# USBWandler.net
KiCad netlist of a schematic drawn in Altium Designer
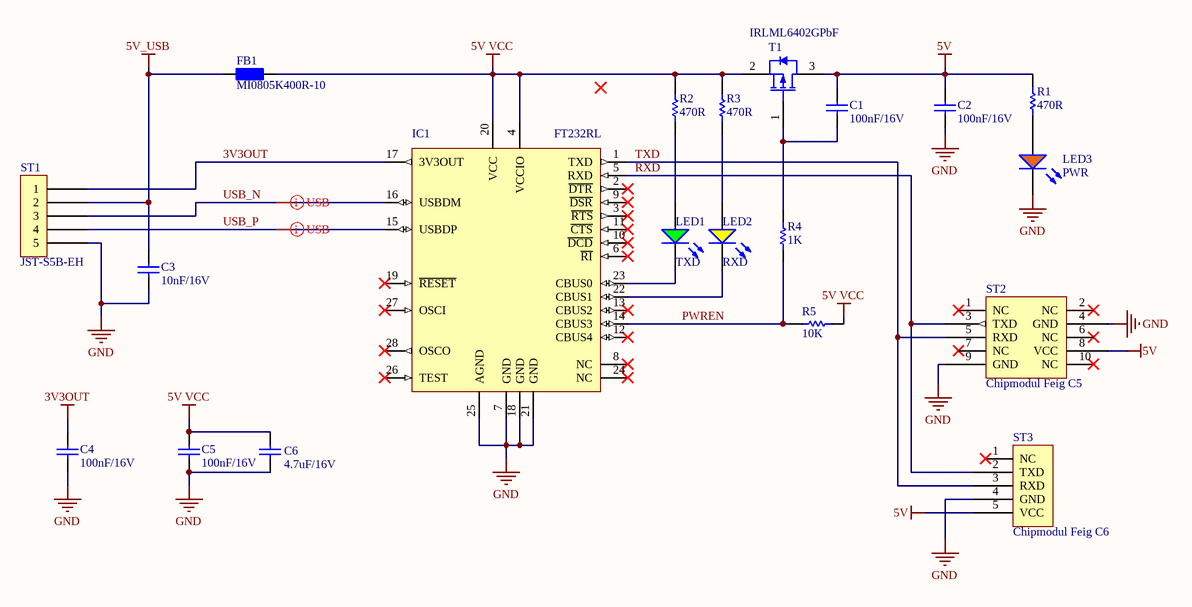
[diagram p0: USBWandler.SchDoc]

(export (version "E")
  (design (tool "Eeschema 10.0.6"))
  (components
    (comp (ref "C1")
      (value "100nF/16V")
      (footprint "CAPC0805(2012)145_M")
      (description "CAP 100nF 16V ±10% 0805 (2012 Metric) Thickness 1.45mm SMD")
      (fields (field (name "TOLERANCE") "Â±10%"))
      (libsource (lib "Altium Content Vault") (part "CMP-1036-04401-1"))
    )
    (comp (ref "C2")
      (value "100nF/16V")
      (footprint "CAPC0805(2012)145_M")
      (description "CAP 100nF 16V ±10% 0805 (2012 Metric) Thickness 1.45mm SMD")
      (fields (field (name "TOLERANCE") "Â±10%"))
      (libsource (lib "Altium Content Vault") (part "CMP-1036-04401-1"))
    )
    (comp (ref "C3")
      (value "10nF/16V")
      (footprint "CAPC0805(2012)145_L")
      (description "CAP 10nF 16V ±1% 0805 (2012 Metric) Thickness 1.45mm SMD")
      (fields (field (name "TOLERANCE") "Â±1%"))
      (libsource (lib "Altium Content Vault") (part "CMP-1036-03813-1"))
    )
    (comp (ref "C4")
      (value "100nF/16V")
      (footprint "CAPC0805(2012)145_M")
      (description "CAP 100nF 16V ±10% 0805 (2012 Metric) Thickness 1.45mm SMD")
      (fields (field (name "TOLERANCE") "Â±10%"))
      (libsource (lib "Altium Content Vault") (part "CMP-1036-04401-1"))
    )
    (comp (ref "C5")
      (value "100nF/16V")
      (footprint "CAPC0805(2012)145_M")
      (description "CAP 100nF 16V ±10% 0805 (2012 Metric) Thickness 1.45mm SMD")
      (fields (field (name "TOLERANCE") "Â±10%"))
      (libsource (lib "Altium Content Vault") (part "CMP-1036-04401-1"))
    )
    (comp (ref "C6")
      (value "4.7uF/16V")
      (footprint "CAPC1206(3216)190_L")
      (description "CAP 4.7uF 16V ±20% 1206 (3216 Metric) Thickness 1.9mm SMD")
      (fields (field (name "TOLERANCE") "Â±20%"))
      (libsource (lib "Altium Content Vault") (part "CMP-1037-04912-1"))
    )
    (comp (ref "FB1")
      (value "MI0805K400R-10")
      (footprint "L0805 (2012)")
      (description "Ferrite Chip Beads MI0805K400R-10, 0805, 40 ohm, 1,5A")
      (libsource (lib "FroH1") (part "Ferrit Bead MI0805K400R-10"))
    )
    (comp (ref "IC1")
      (value "FT232RL")
      (footprint "SSOP-28_M")
      (description "USB UART Asynchronous Serial Data Transfer Chip, 28-pin SSOP, Tape and Reel")
      (fields (field (name "PARTNUMBER") "FT232RL-Reel") (field (name "MANUFACTURER") "FTDI"))
      (libsource (lib "Altium Content Vault") (part "CMP-0078-00029-3"))
    )
    (comp (ref "LED1")
      (value "TXD")
      (footprint "LTST-C170GKT_V")
      (description "LED GREEN CLEAR 0805 SMD")
      (fields (field (name "PARTNUMBER") "LTST-C170GKT"))
      (libsource (lib "Altium Content Vault") (part "CMP-1674-00002-2"))
    )
    (comp (ref "LED2")
      (value "RXD")
      (footprint "LTST-C170YKT_V")
      (description "LED YELLOW CLEAR 0805 SMD")
      (fields (field (name "MANUFACTURER") "Lite-On") (field (name "PARTNUMBER") "LTST-C170YKT"))
      (libsource (lib "Altium Content Vault") (part "CMP-1674-00003-3"))
    )
    (comp (ref "LED3")
      (value "PWR")
      (footprint "LTST-C171AKT_V")
      (description "LED AMBER CLR THIN 0805 SMD")
      (fields (field (name "PARTNUMBER") "LTST-C171AKT") (field (name "MANUFACTURER") "Lite-On"))
      (libsource (lib "Altium Content Vault") (part "CMP-1674-00004-3"))
    )
    (comp (ref "R1")
      (value "470R")
      (footprint "RESC0805(2012)_N")
      (description "470R 0.125W 1% 0805 (2012 Metric)  SMD")
      (fields (field (name "POWER") "0.125 W") (field (name "TOLERANCE") "1 %"))
      (libsource (lib "Altium Content Vault") (part "CMP-1013-00473-1"))
    )
    (comp (ref "R2")
      (value "470R")
      (footprint "RESC0805(2012)_N")
      (description "470R 0.125W 1% 0805 (2012 Metric)  SMD")
      (fields (field (name "POWER") "0.125 W") (field (name "TOLERANCE") "1 %"))
      (libsource (lib "Altium Content Vault") (part "CMP-1013-00473-1"))
    )
    (comp (ref "R3")
      (value "470R")
      (footprint "RESC0805(2012)_N")
      (description "470R 0.125W 1% 0805 (2012 Metric)  SMD")
      (fields (field (name "POWER") "0.125 W") (field (name "TOLERANCE") "1 %"))
      (libsource (lib "Altium Content Vault") (part "CMP-1013-00473-1"))
    )
    (comp (ref "R4")
      (value "1K")
      (footprint "RESC0805(2012)_M")
      (description "1K 0.125W 1% 0805 (2012 Metric)  SMD")
      (fields (field (name "TOLERANCE") "1 %") (field (name "POWER") "0.125 W"))
      (libsource (lib "Altium Content Vault") (part "CMP-1013-00510-1"))
    )
    (comp (ref "R5")
      (value "10K")
      (footprint "RESC0805(2012)_M")
      (description "10K 0.125W 1% 0805 (2012 Metric)  SMD")
      (fields (field (name "TOLERANCE") "1 %") (field (name "POWER") "0.125 W"))
      (libsource (lib "Altium Content Vault") (part "CMP-1013-00623-1"))
    )
    (comp (ref "ST1")
      (value "JST-S5B-EH")
      (footprint "JST-S5B-EH")
      (description "JST EH Connector RM=2,5mm, Side Entry Type")
      (libsource (lib "FroH1") (part "JST-S5B-EH"))
    )
    (comp (ref "ST2")
      (value "Chipmodul Feig C5")
      (footprint "FroH1:ChipModul Feig C5")
      (description "Feig Chipmodul CPR.02")
      (libsource (lib "FroH1") (part "Chipmodul Feig C5"))
    )
    (comp (ref "ST3")
      (value "Chipmodul Feig C6")
      (footprint "ChipModul Feig C6")
      (libsource (lib "FroH1") (part "Chipmodul Feig C6"))
    )
    (comp (ref "T1")
      (value "IRLML6402GPbF")
      (footprint "INTR-SOT-23-3_V")
      (description "HEXFET Power MOSFET, P-Channel, -20 V VDSS, 0.065 Ohm RDS, 3-Pin SOT23, RoHS, Tape and Reel")
      (fields (field (name "MANUFACTURER") "International Rectifier"))
      (libsource (lib "Altium Content Vault") (part "CMP-0676-00001-1"))
    )
  )
  (nets
    (net (code "1") (name "/PWREN") (class "Default")
      (node (ref "IC1") (pin "14") (pinfunction "CBUS3_14") (pintype "bidirectional"))
      (node (ref "R4") (pin "1") (pinfunction "1_1") (pintype "passive"))
      (node (ref "R5") (pin "2") (pinfunction "2_2") (pintype "passive"))
    )
    (net (code "2") (name "/RXD") (class "Default")
      (node (ref "IC1") (pin "5") (pinfunction "RXD_5") (pintype "input"))
      (node (ref "ST2") (pin "3") (pinfunction "TXD_3") (pintype "output"))
      (node (ref "ST3") (pin "2") (pinfunction "TXD_2") (pintype "passive"))
    )
    (net (code "3") (name "/TXD") (class "Default")
      (node (ref "IC1") (pin "1") (pinfunction "TXD_1") (pintype "output"))
      (node (ref "ST2") (pin "5") (pinfunction "RXD_5") (pintype "passive"))
      (node (ref "ST3") (pin "3") (pinfunction "RXD_3") (pintype "passive"))
    )
    (net (code "4") (name "/USB_N") (class "Default")
      (node (ref "IC1") (pin "16") (pinfunction "USBDM_16") (pintype "bidirectional"))
      (node (ref "ST1") (pin "3") (pinfunction "3_3") (pintype "passive"))
    )
    (net (code "5") (name "/USB_P") (class "Default")
      (node (ref "IC1") (pin "15") (pinfunction "USBDP_15") (pintype "bidirectional"))
      (node (ref "ST1") (pin "4") (pinfunction "4_4") (pintype "passive"))
    )
    (net (code "6") (name "3V3OUT") (class "Default")
      (node (ref "C4") (pin "2") (pinfunction "2_2") (pintype "passive"))
      (node (ref "IC1") (pin "17") (pinfunction "3V3OUT_17") (pintype "output"))
      (node (ref "ST1") (pin "1") (pinfunction "1_1") (pintype "passive"))
    )
    (net (code "7") (name "5V") (class "Default")
      (node (ref "C1") (pin "2") (pinfunction "2_2") (pintype "passive"))
      (node (ref "C2") (pin "2") (pinfunction "2_2") (pintype "passive"))
      (node (ref "R1") (pin "2") (pinfunction "2_2") (pintype "passive"))
      (node (ref "ST2") (pin "8") (pinfunction "VCC_8") (pintype "power_in"))
      (node (ref "ST3") (pin "5") (pinfunction "VCC_5") (pintype "power_in"))
      (node (ref "T1") (pin "3") (pinfunction "D_3") (pintype "passive"))
    )
    (net (code "8") (name "5V VCC") (class "Default")
      (node (ref "C5") (pin "2") (pinfunction "2_2") (pintype "passive"))
      (node (ref "C6") (pin "2") (pinfunction "2_2") (pintype "passive"))
      (node (ref "FB1") (pin "2") (pinfunction "2_2") (pintype "passive"))
      (node (ref "IC1") (pin "20") (pinfunction "VCC_20") (pintype "power_in"))
      (node (ref "IC1") (pin "4") (pinfunction "VCCIO_4") (pintype "power_in"))
      (node (ref "R2") (pin "2") (pinfunction "2_2") (pintype "passive"))
      (node (ref "R3") (pin "2") (pinfunction "2_2") (pintype "passive"))
      (node (ref "R5") (pin "1") (pinfunction "1_1") (pintype "passive"))
      (node (ref "T1") (pin "2") (pinfunction "S_2") (pintype "passive"))
    )
    (net (code "9") (name "5V_USB") (class "Default")
      (node (ref "C3") (pin "2") (pinfunction "2_2") (pintype "passive"))
      (node (ref "FB1") (pin "1") (pinfunction "1_1") (pintype "passive"))
      (node (ref "ST1") (pin "2") (pinfunction "2_2") (pintype "passive"))
    )
    (net (code "10") (name "GND") (class "Default")
      (node (ref "C2") (pin "1") (pinfunction "1_1") (pintype "passive"))
      (node (ref "C3") (pin "1") (pinfunction "1_1") (pintype "passive"))
      (node (ref "C4") (pin "1") (pinfunction "1_1") (pintype "passive"))
      (node (ref "C5") (pin "1") (pinfunction "1_1") (pintype "passive"))
      (node (ref "C6") (pin "1") (pinfunction "1_1") (pintype "passive"))
      (node (ref "IC1") (pin "18") (pinfunction "GND_18") (pintype "power_in"))
      (node (ref "IC1") (pin "21") (pinfunction "GND_21") (pintype "power_in"))
      (node (ref "IC1") (pin "25") (pinfunction "AGND_25") (pintype "power_in"))
      (node (ref "IC1") (pin "7") (pinfunction "GND_7") (pintype "power_in"))
      (node (ref "LED3") (pin "C") (pinfunction "C_C") (pintype "passive"))
      (node (ref "ST1") (pin "5") (pinfunction "5_5") (pintype "passive"))
      (node (ref "ST2") (pin "4") (pinfunction "GND_4") (pintype "power_in"))
      (node (ref "ST2") (pin "9") (pinfunction "GND_9") (pintype "power_in"))
      (node (ref "ST3") (pin "4") (pinfunction "GND_4") (pintype "power_in"))
    )
    (net (code "11") (name "Net-(IC1-CBUS0)") (class "Default")
      (node (ref "IC1") (pin "23") (pinfunction "CBUS0_23") (pintype "bidirectional"))
      (node (ref "LED1") (pin "C") (pinfunction "C_C") (pintype "passive"))
    )
    (net (code "12") (name "Net-(IC1-CBUS1)") (class "Default")
      (node (ref "IC1") (pin "22") (pinfunction "CBUS1_22") (pintype "bidirectional"))
      (node (ref "LED2") (pin "C") (pinfunction "C_C") (pintype "passive"))
    )
    (net (code "13") (name "Net-(LED1-PadA)") (class "Default")
      (node (ref "LED1") (pin "A") (pinfunction "A_A") (pintype "passive"))
      (node (ref "R2") (pin "1") (pinfunction "1_1") (pintype "passive"))
    )
    (net (code "14") (name "Net-(LED2-PadA)") (class "Default")
      (node (ref "LED2") (pin "A") (pinfunction "A_A") (pintype "passive"))
      (node (ref "R3") (pin "1") (pinfunction "1_1") (pintype "passive"))
    )
    (net (code "15") (name "Net-(LED3-PadA)") (class "Default")
      (node (ref "LED3") (pin "A") (pinfunction "A_A") (pintype "passive"))
      (node (ref "R1") (pin "1") (pinfunction "1_1") (pintype "passive"))
    )
    (net (code "16") (name "Net-(T1-G)") (class "Default")
      (node (ref "C1") (pin "1") (pinfunction "1_1") (pintype "passive"))
      (node (ref "R4") (pin "2") (pinfunction "2_2") (pintype "passive"))
      (node (ref "T1") (pin "1") (pinfunction "G_1") (pintype "passive"))
    )
    (net (code "17") (name "unconnected-(IC1-CBUS2-Pad13)") (class "Default")
      (node (ref "IC1") (pin "13") (pinfunction "CBUS2_13") (pintype "bidirectional+no_connect"))
    )
    (net (code "18") (name "unconnected-(IC1-CBUS4-Pad12)") (class "Default")
      (node (ref "IC1") (pin "12") (pinfunction "CBUS4_12") (pintype "bidirectional+no_connect"))
    )
    (net (code "19") (name "unconnected-(IC1-NC-Pad8)") (class "Default")
      (node (ref "IC1") (pin "8") (pinfunction "NC_8") (pintype "passive+no_connect"))
    )
    (net (code "20") (name "unconnected-(IC1-NC-Pad24)") (class "Default")
      (node (ref "IC1") (pin "24") (pinfunction "NC_24") (pintype "passive+no_connect"))
    )
    (net (code "21") (name "unconnected-(IC1-OSCI-Pad27)") (class "Default")
      (node (ref "IC1") (pin "27") (pinfunction "OSCI_27") (pintype "input+no_connect"))
    )
    (net (code "22") (name "unconnected-(IC1-OSCO-Pad28)") (class "Default")
      (node (ref "IC1") (pin "28") (pinfunction "OSCO_28") (pintype "output+no_connect"))
    )
    (net (code "23") (name "unconnected-(IC1-TEST-Pad26)") (class "Default")
      (node (ref "IC1") (pin "26") (pinfunction "TEST_26") (pintype "input+no_connect"))
    )
    (net (code "24") (name "unconnected-(IC1-~{CTS}-Pad11)") (class "Default")
      (node (ref "IC1") (pin "11") (pinfunction "~{CTS}_11") (pintype "input+no_connect"))
    )
    (net (code "25") (name "unconnected-(IC1-~{DCD}-Pad10)") (class "Default")
      (node (ref "IC1") (pin "10") (pinfunction "~{DCD}_10") (pintype "input+no_connect"))
    )
    (net (code "26") (name "unconnected-(IC1-~{DSR}-Pad9)") (class "Default")
      (node (ref "IC1") (pin "9") (pinfunction "~{DSR}_9") (pintype "input+no_connect"))
    )
    (net (code "27") (name "unconnected-(IC1-~{DTR}-Pad2)") (class "Default")
      (node (ref "IC1") (pin "2") (pinfunction "~{DTR}_2") (pintype "output+no_connect"))
    )
    (net (code "28") (name "unconnected-(IC1-~{RESET}-Pad19)") (class "Default")
      (node (ref "IC1") (pin "19") (pinfunction "~{RESET}_19") (pintype "input+no_connect"))
    )
    (net (code "29") (name "unconnected-(IC1-~{RI}-Pad6)") (class "Default")
      (node (ref "IC1") (pin "6") (pinfunction "~{RI}_6") (pintype "input+no_connect"))
    )
    (net (code "30") (name "unconnected-(IC1-~{RTS}-Pad3)") (class "Default")
      (node (ref "IC1") (pin "3") (pinfunction "~{RTS}_3") (pintype "output+no_connect"))
    )
    (net (code "31") (name "unconnected-(ST2-NC-Pad1)") (class "Default")
      (node (ref "ST2") (pin "1") (pinfunction "NC_1") (pintype "passive+no_connect"))
    )
    (net (code "32") (name "unconnected-(ST2-NC-Pad2)") (class "Default")
      (node (ref "ST2") (pin "2") (pinfunction "NC_2") (pintype "passive+no_connect"))
    )
    (net (code "33") (name "unconnected-(ST2-NC-Pad6)") (class "Default")
      (node (ref "ST2") (pin "6") (pinfunction "NC_6") (pintype "passive+no_connect"))
    )
    (net (code "34") (name "unconnected-(ST2-NC-Pad7)") (class "Default")
      (node (ref "ST2") (pin "7") (pinfunction "NC_7") (pintype "passive+no_connect"))
    )
    (net (code "35") (name "unconnected-(ST2-NC-Pad10)") (class "Default")
      (node (ref "ST2") (pin "10") (pinfunction "NC_10") (pintype "passive+no_connect"))
    )
    (net (code "36") (name "unconnected-(ST3-NC-Pad1)") (class "Default")
      (node (ref "ST3") (pin "1") (pinfunction "NC_1") (pintype "passive+no_connect"))
    )
  )
)
